# lowerkit.net
KiCad netlist of a schematic drawn in EAGLE
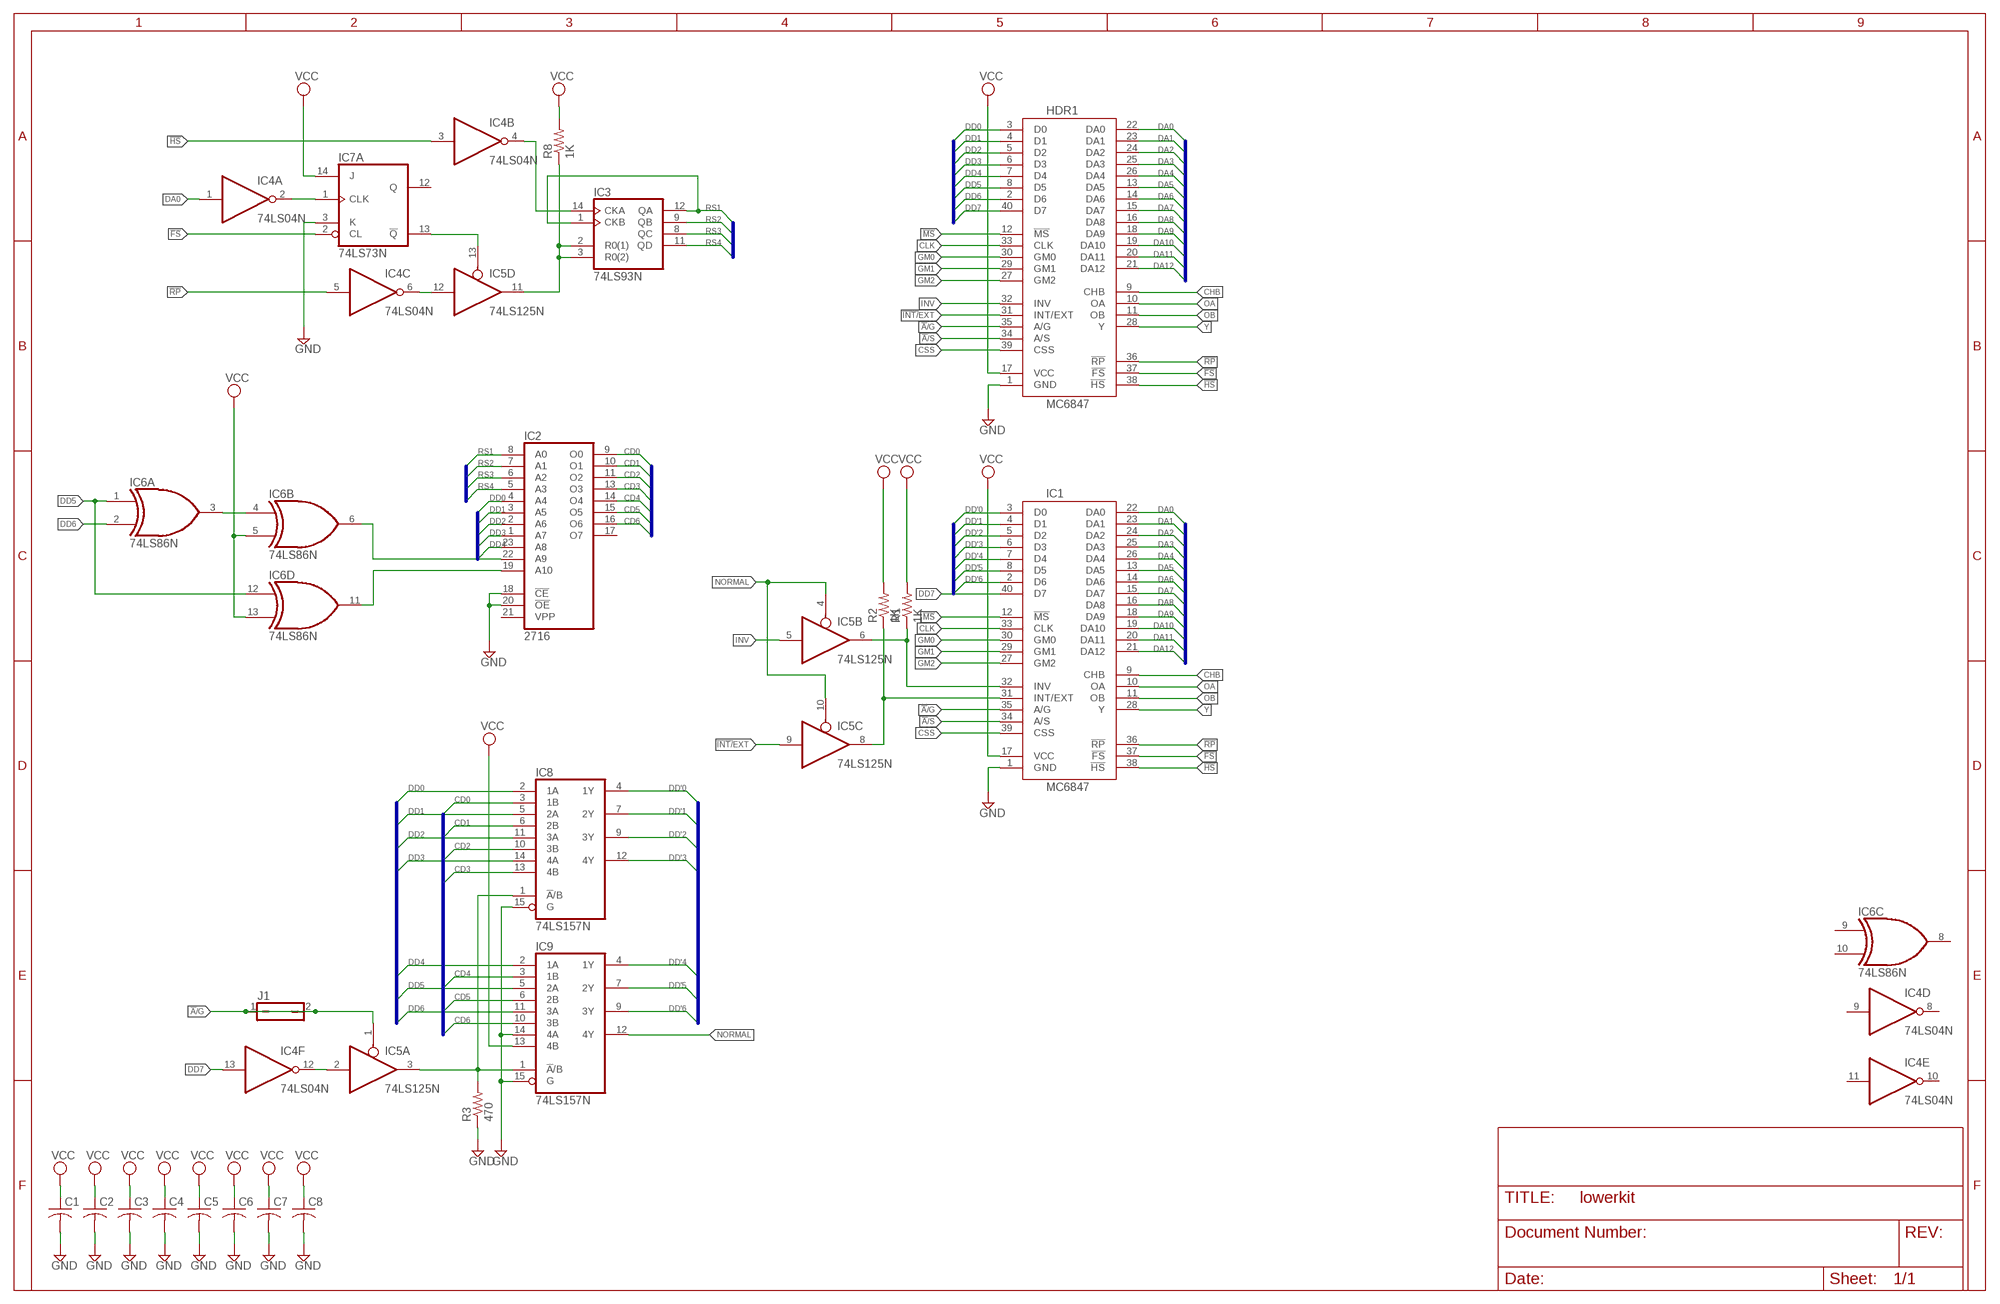
[diagram p0: schematic, sheet 1]

(export (version "E")
  (design (tool "Eeschema 10.0.6"))
  (components
    (comp (ref "C1")
      (value "C-US025-025X050")
      (footprint "eagle-import:C025-025X050")
      (libsource (lib "eagle-import") (part "C-US025-025X050"))
    )
    (comp (ref "C2")
      (value "C-US025-025X050")
      (footprint "eagle-import:C025-025X050")
      (libsource (lib "eagle-import") (part "C-US025-025X050"))
    )
    (comp (ref "C3")
      (value "C-US025-025X050")
      (footprint "eagle-import:C025-025X050")
      (libsource (lib "eagle-import") (part "C-US025-025X050"))
    )
    (comp (ref "C4")
      (value "C-US025-025X050")
      (footprint "eagle-import:C025-025X050")
      (libsource (lib "eagle-import") (part "C-US025-025X050"))
    )
    (comp (ref "C5")
      (value "C-US025-025X050")
      (footprint "eagle-import:C025-025X050")
      (libsource (lib "eagle-import") (part "C-US025-025X050"))
    )
    (comp (ref "C6")
      (value "C-US025-025X050")
      (footprint "eagle-import:C025-025X050")
      (libsource (lib "eagle-import") (part "C-US025-025X050"))
    )
    (comp (ref "C7")
      (value "C-US025-025X050")
      (footprint "eagle-import:C025-025X050")
      (libsource (lib "eagle-import") (part "C-US025-025X050"))
    )
    (comp (ref "C8")
      (value "C-US025-025X050")
      (footprint "eagle-import:C025-025X050")
      (libsource (lib "eagle-import") (part "C-US025-025X050"))
    )
    (comp (ref "HDR1")
      (value "MC6847")
      (footprint "eagle-import:DIP-40")
      (libsource (lib "eagle-import") (part "MC6847"))
    )
    (comp (ref "IC1")
      (value "MC6847")
      (footprint "eagle-import:DIP-40")
      (libsource (lib "eagle-import") (part "MC6847"))
    )
    (comp (ref "IC2")
      (value "2716")
      (footprint "eagle-import:DIL24")
      (libsource (lib "eagle-import") (part "2716"))
    )
    (comp (ref "IC3")
      (value "74LS93N")
      (footprint "eagle-import:DIL14-RP")
      (libsource (lib "eagle-import") (part "7493NLS"))
    )
    (comp (ref "IC4")
      (value "74LS04N")
      (footprint "eagle-import:DIL14-RP")
      (libsource (lib "eagle-import") (part "7404NLS"))
    )
    (comp (ref "IC5")
      (value "74LS125N")
      (footprint "eagle-import:DIL14-RP")
      (libsource (lib "eagle-import") (part "74125NLS"))
    )
    (comp (ref "IC6")
      (value "74LS86N")
      (footprint "eagle-import:DIL14-RP")
      (libsource (lib "eagle-import") (part "7486NLS"))
    )
    (comp (ref "IC7")
      (value "74LS73N")
      (footprint "eagle-import:DIL14-RP")
      (libsource (lib "eagle-import") (part "7473NLS"))
    )
    (comp (ref "IC8")
      (value "74LS157N")
      (footprint "eagle-import:DIL16-RP")
      (libsource (lib "eagle-import") (part "74157NLS"))
    )
    (comp (ref "IC9")
      (value "74LS157N")
      (footprint "eagle-import:DIL16-RP")
      (libsource (lib "eagle-import") (part "74157NLS"))
    )
    (comp (ref "J1")
      (value "JP1Q")
      (footprint "eagle-import:JP1")
      (libsource (lib "eagle-import") (part "JP1Q"))
    )
    (comp (ref "R1")
      (value "1K")
      (footprint "eagle-import:0204_7")
      (libsource (lib "eagle-import") (part "R-US_0204/7"))
    )
    (comp (ref "R2")
      (value "1K")
      (footprint "eagle-import:0204_7")
      (libsource (lib "eagle-import") (part "R-US_0204/7"))
    )
    (comp (ref "R3")
      (value "470")
      (footprint "eagle-import:0204_7")
      (libsource (lib "eagle-import") (part "R-US_0204/7"))
    )
    (comp (ref "R8")
      (value "1K")
      (footprint "eagle-import:0204_7")
      (libsource (lib "eagle-import") (part "R-US_0204/7"))
    )
  )
  (nets
    (net (code "1") (name "/CD0") (class "Default")
      (node (ref "IC2") (pin "9") (pinfunction "O0_9") (pintype "tri_state"))
      (node (ref "IC8") (pin "3") (pinfunction "1B_3") (pintype "input"))
    )
    (net (code "2") (name "/CD1") (class "Default")
      (node (ref "IC2") (pin "10") (pinfunction "O1_10") (pintype "tri_state"))
      (node (ref "IC8") (pin "6") (pinfunction "2B_6") (pintype "input"))
    )
    (net (code "3") (name "/CD2") (class "Default")
      (node (ref "IC2") (pin "11") (pinfunction "O2_11") (pintype "tri_state"))
      (node (ref "IC8") (pin "10") (pinfunction "3B_10") (pintype "input"))
    )
    (net (code "4") (name "/CD3") (class "Default")
      (node (ref "IC2") (pin "13") (pinfunction "O3_13") (pintype "tri_state"))
      (node (ref "IC8") (pin "13") (pinfunction "4B_13") (pintype "input"))
    )
    (net (code "5") (name "/CD4") (class "Default")
      (node (ref "IC2") (pin "14") (pinfunction "O4_14") (pintype "tri_state"))
      (node (ref "IC9") (pin "3") (pinfunction "1B_3") (pintype "input"))
    )
    (net (code "6") (name "/CD5") (class "Default")
      (node (ref "IC2") (pin "15") (pinfunction "O5_15") (pintype "tri_state"))
      (node (ref "IC9") (pin "6") (pinfunction "2B_6") (pintype "input"))
    )
    (net (code "7") (name "/CD6") (class "Default")
      (node (ref "IC2") (pin "16") (pinfunction "O6_16") (pintype "tri_state"))
      (node (ref "IC9") (pin "10") (pinfunction "3B_10") (pintype "input"))
    )
    (net (code "8") (name "/DA1") (class "Default")
      (node (ref "HDR1") (pin "23") (pinfunction "DA1_23") (pintype "bidirectional"))
      (node (ref "IC1") (pin "23") (pinfunction "DA1_23") (pintype "bidirectional"))
    )
    (net (code "9") (name "/DA2") (class "Default")
      (node (ref "HDR1") (pin "24") (pinfunction "DA2_24") (pintype "bidirectional"))
      (node (ref "IC1") (pin "24") (pinfunction "DA2_24") (pintype "bidirectional"))
    )
    (net (code "10") (name "/DA3") (class "Default")
      (node (ref "HDR1") (pin "25") (pinfunction "DA3_25") (pintype "bidirectional"))
      (node (ref "IC1") (pin "25") (pinfunction "DA3_25") (pintype "bidirectional"))
    )
    (net (code "11") (name "/DA4") (class "Default")
      (node (ref "HDR1") (pin "26") (pinfunction "DA4_26") (pintype "bidirectional"))
      (node (ref "IC1") (pin "26") (pinfunction "DA4_26") (pintype "bidirectional"))
    )
    (net (code "12") (name "/DA5") (class "Default")
      (node (ref "HDR1") (pin "13") (pinfunction "DA5_13") (pintype "bidirectional"))
      (node (ref "IC1") (pin "13") (pinfunction "DA5_13") (pintype "bidirectional"))
    )
    (net (code "13") (name "/DA6") (class "Default")
      (node (ref "HDR1") (pin "14") (pinfunction "DA6_14") (pintype "bidirectional"))
      (node (ref "IC1") (pin "14") (pinfunction "DA6_14") (pintype "bidirectional"))
    )
    (net (code "14") (name "/DA7") (class "Default")
      (node (ref "HDR1") (pin "15") (pinfunction "DA7_15") (pintype "bidirectional"))
      (node (ref "IC1") (pin "15") (pinfunction "DA7_15") (pintype "bidirectional"))
    )
    (net (code "15") (name "/DA8") (class "Default")
      (node (ref "HDR1") (pin "16") (pinfunction "DA8_16") (pintype "bidirectional"))
      (node (ref "IC1") (pin "16") (pinfunction "DA8_16") (pintype "bidirectional"))
    )
    (net (code "16") (name "/DA9") (class "Default")
      (node (ref "HDR1") (pin "18") (pinfunction "DA9_18") (pintype "bidirectional"))
      (node (ref "IC1") (pin "18") (pinfunction "DA9_18") (pintype "bidirectional"))
    )
    (net (code "17") (name "/DA10") (class "Default")
      (node (ref "HDR1") (pin "19") (pinfunction "DA10_19") (pintype "bidirectional"))
      (node (ref "IC1") (pin "19") (pinfunction "DA10_19") (pintype "bidirectional"))
    )
    (net (code "18") (name "/DA11") (class "Default")
      (node (ref "HDR1") (pin "20") (pinfunction "DA11_20") (pintype "bidirectional"))
      (node (ref "IC1") (pin "20") (pinfunction "DA11_20") (pintype "bidirectional"))
    )
    (net (code "19") (name "/DA12") (class "Default")
      (node (ref "HDR1") (pin "21") (pinfunction "DA12_21") (pintype "bidirectional"))
      (node (ref "IC1") (pin "21") (pinfunction "DA12_21") (pintype "bidirectional"))
    )
    (net (code "20") (name "/DD'0") (class "Default")
      (node (ref "IC1") (pin "3") (pinfunction "D0_3") (pintype "bidirectional"))
      (node (ref "IC8") (pin "4") (pinfunction "1Y_4") (pintype "output"))
    )
    (net (code "21") (name "/DD'1") (class "Default")
      (node (ref "IC1") (pin "4") (pinfunction "D1_4") (pintype "bidirectional"))
      (node (ref "IC8") (pin "7") (pinfunction "2Y_7") (pintype "output"))
    )
    (net (code "22") (name "/DD'2") (class "Default")
      (node (ref "IC1") (pin "5") (pinfunction "D2_5") (pintype "bidirectional"))
      (node (ref "IC8") (pin "9") (pinfunction "3Y_9") (pintype "output"))
    )
    (net (code "23") (name "/DD'3") (class "Default")
      (node (ref "IC1") (pin "6") (pinfunction "D3_6") (pintype "bidirectional"))
      (node (ref "IC8") (pin "12") (pinfunction "4Y_12") (pintype "output"))
    )
    (net (code "24") (name "/DD'4") (class "Default")
      (node (ref "IC1") (pin "7") (pinfunction "D4_7") (pintype "bidirectional"))
      (node (ref "IC9") (pin "4") (pinfunction "1Y_4") (pintype "output"))
    )
    (net (code "25") (name "/DD'5") (class "Default")
      (node (ref "IC1") (pin "8") (pinfunction "D5_8") (pintype "bidirectional"))
      (node (ref "IC9") (pin "7") (pinfunction "2Y_7") (pintype "output"))
    )
    (net (code "26") (name "/DD'6") (class "Default")
      (node (ref "IC1") (pin "2") (pinfunction "D6_2") (pintype "bidirectional"))
      (node (ref "IC9") (pin "9") (pinfunction "3Y_9") (pintype "output"))
    )
    (net (code "27") (name "/DD0") (class "Default")
      (node (ref "HDR1") (pin "3") (pinfunction "D0_3") (pintype "bidirectional"))
      (node (ref "IC2") (pin "4") (pinfunction "A4_4") (pintype "input"))
      (node (ref "IC8") (pin "2") (pinfunction "1A_2") (pintype "input"))
    )
    (net (code "28") (name "/DD1") (class "Default")
      (node (ref "HDR1") (pin "4") (pinfunction "D1_4") (pintype "bidirectional"))
      (node (ref "IC2") (pin "3") (pinfunction "A5_3") (pintype "input"))
      (node (ref "IC8") (pin "5") (pinfunction "2A_5") (pintype "input"))
    )
    (net (code "29") (name "/DD2") (class "Default")
      (node (ref "HDR1") (pin "5") (pinfunction "D2_5") (pintype "bidirectional"))
      (node (ref "IC2") (pin "2") (pinfunction "A6_2") (pintype "input"))
      (node (ref "IC8") (pin "11") (pinfunction "3A_11") (pintype "input"))
    )
    (net (code "30") (name "/DD3") (class "Default")
      (node (ref "HDR1") (pin "6") (pinfunction "D3_6") (pintype "bidirectional"))
      (node (ref "IC2") (pin "1") (pinfunction "A7_1") (pintype "input"))
      (node (ref "IC8") (pin "14") (pinfunction "4A_14") (pintype "input"))
    )
    (net (code "31") (name "/DD4") (class "Default")
      (node (ref "HDR1") (pin "7") (pinfunction "D4_7") (pintype "bidirectional"))
      (node (ref "IC2") (pin "23") (pinfunction "A8_23") (pintype "input"))
      (node (ref "IC9") (pin "2") (pinfunction "1A_2") (pintype "input"))
    )
    (net (code "32") (name "/RS1") (class "Default")
      (node (ref "IC2") (pin "8") (pinfunction "A0_8") (pintype "input"))
      (node (ref "IC3") (pin "1") (pinfunction "CKB_1") (pintype "input"))
      (node (ref "IC3") (pin "12") (pinfunction "QA_12") (pintype "output"))
    )
    (net (code "33") (name "/RS2") (class "Default")
      (node (ref "IC2") (pin "7") (pinfunction "A1_7") (pintype "input"))
      (node (ref "IC3") (pin "9") (pinfunction "QB_9") (pintype "output"))
    )
    (net (code "34") (name "/RS3") (class "Default")
      (node (ref "IC2") (pin "6") (pinfunction "A2_6") (pintype "input"))
      (node (ref "IC3") (pin "8") (pinfunction "QC_8") (pintype "output"))
    )
    (net (code "35") (name "/RS4") (class "Default")
      (node (ref "IC2") (pin "5") (pinfunction "A3_5") (pintype "input"))
      (node (ref "IC3") (pin "11") (pinfunction "QD_11") (pintype "output"))
    )
    (net (code "36") (name "/~{A}{slash}G") (class "Default")
      (node (ref "HDR1") (pin "35") (pinfunction "A/G_35") (pintype "bidirectional"))
      (node (ref "IC1") (pin "35") (pinfunction "A/G_35") (pintype "bidirectional"))
      (node (ref "IC5") (pin "1") (pinfunction "OE_1") (pintype "input"))
      (node (ref "J1") (pin "1") (pinfunction "1_1") (pintype "passive"))
      (node (ref "J1") (pin "2") (pinfunction "2_2") (pintype "passive"))
    )
    (net (code "37") (name "/~{A}{slash}S") (class "Default")
      (node (ref "HDR1") (pin "34") (pinfunction "A/S_34") (pintype "bidirectional"))
      (node (ref "IC1") (pin "34") (pinfunction "A/S_34") (pintype "bidirectional"))
    )
    (net (code "38") (name "/~{FS}") (class "Default")
      (node (ref "HDR1") (pin "37") (pinfunction "~{FS}_37") (pintype "bidirectional"))
      (node (ref "IC1") (pin "37") (pinfunction "~{FS}_37") (pintype "bidirectional"))
      (node (ref "IC7") (pin "2") (pinfunction "CL_2") (pintype "input"))
    )
    (net (code "39") (name "/~{HS}") (class "Default")
      (node (ref "HDR1") (pin "38") (pinfunction "~{HS}_38") (pintype "bidirectional"))
      (node (ref "IC1") (pin "38") (pinfunction "~{HS}_38") (pintype "bidirectional"))
      (node (ref "IC4") (pin "3") (pinfunction "I_3") (pintype "input"))
    )
    (net (code "40") (name "/~{INT{slash}}EXT") (class "Default")
      (node (ref "HDR1") (pin "31") (pinfunction "INT/EXT_31") (pintype "bidirectional"))
      (node (ref "IC5") (pin "9") (pinfunction "I_9") (pintype "input"))
    )
    (net (code "41") (name "/~{MS}") (class "Default")
      (node (ref "HDR1") (pin "12") (pinfunction "~{MS}_12") (pintype "bidirectional"))
      (node (ref "IC1") (pin "12") (pinfunction "~{MS}_12") (pintype "bidirectional"))
    )
    (net (code "42") (name "/~{RP}") (class "Default")
      (node (ref "HDR1") (pin "36") (pinfunction "~{RP}_36") (pintype "bidirectional"))
      (node (ref "IC1") (pin "36") (pinfunction "~{RP}_36") (pintype "bidirectional"))
      (node (ref "IC4") (pin "5") (pinfunction "I_5") (pintype "input"))
    )
    (net (code "43") (name "CHB") (class "Default")
      (node (ref "HDR1") (pin "9") (pinfunction "CHB_9") (pintype "bidirectional"))
      (node (ref "IC1") (pin "9") (pinfunction "CHB_9") (pintype "bidirectional"))
    )
    (net (code "44") (name "CLK") (class "Default")
      (node (ref "HDR1") (pin "33") (pinfunction "CLK_33") (pintype "bidirectional"))
      (node (ref "IC1") (pin "33") (pinfunction "CLK_33") (pintype "bidirectional"))
    )
    (net (code "45") (name "CSS") (class "Default")
      (node (ref "HDR1") (pin "39") (pinfunction "CSS_39") (pintype "bidirectional"))
      (node (ref "IC1") (pin "39") (pinfunction "CSS_39") (pintype "bidirectional"))
    )
    (net (code "46") (name "DA0") (class "Default")
      (node (ref "HDR1") (pin "22") (pinfunction "DA0_22") (pintype "bidirectional"))
      (node (ref "IC1") (pin "22") (pinfunction "DA0_22") (pintype "bidirectional"))
      (node (ref "IC4") (pin "1") (pinfunction "I_1") (pintype "input"))
    )
    (net (code "47") (name "DD5") (class "Default")
      (node (ref "HDR1") (pin "8") (pinfunction "D5_8") (pintype "bidirectional"))
      (node (ref "IC6") (pin "1") (pinfunction "I0_1") (pintype "input"))
      (node (ref "IC6") (pin "12") (pinfunction "I0_12") (pintype "input"))
      (node (ref "IC9") (pin "5") (pinfunction "2A_5") (pintype "input"))
    )
    (net (code "48") (name "DD6") (class "Default")
      (node (ref "HDR1") (pin "2") (pinfunction "D6_2") (pintype "bidirectional"))
      (node (ref "IC6") (pin "2") (pinfunction "I1_2") (pintype "input"))
      (node (ref "IC9") (pin "11") (pinfunction "3A_11") (pintype "input"))
    )
    (net (code "49") (name "DD7") (class "Default")
      (node (ref "HDR1") (pin "40") (pinfunction "D7_40") (pintype "bidirectional"))
      (node (ref "IC1") (pin "40") (pinfunction "D7_40") (pintype "bidirectional"))
      (node (ref "IC4") (pin "13") (pinfunction "I_13") (pintype "input"))
    )
    (net (code "50") (name "GM0") (class "Default")
      (node (ref "HDR1") (pin "30") (pinfunction "GM0_30") (pintype "bidirectional"))
      (node (ref "IC1") (pin "30") (pinfunction "GM0_30") (pintype "bidirectional"))
    )
    (net (code "51") (name "GM1") (class "Default")
      (node (ref "HDR1") (pin "29") (pinfunction "GM1_29") (pintype "bidirectional"))
      (node (ref "IC1") (pin "29") (pinfunction "GM1_29") (pintype "bidirectional"))
    )
    (net (code "52") (name "GM2") (class "Default")
      (node (ref "HDR1") (pin "27") (pinfunction "GM2_27") (pintype "bidirectional"))
      (node (ref "IC1") (pin "27") (pinfunction "GM2_27") (pintype "bidirectional"))
    )
    (net (code "53") (name "GND") (class "Default")
      (node (ref "C1") (pin "2") (pinfunction "2_2") (pintype "passive"))
      (node (ref "C2") (pin "2") (pinfunction "2_2") (pintype "passive"))
      (node (ref "C3") (pin "2") (pinfunction "2_2") (pintype "passive"))
      (node (ref "C4") (pin "2") (pinfunction "2_2") (pintype "passive"))
      (node (ref "C5") (pin "2") (pinfunction "2_2") (pintype "passive"))
      (node (ref "C6") (pin "2") (pinfunction "2_2") (pintype "passive"))
      (node (ref "C7") (pin "2") (pinfunction "2_2") (pintype "passive"))
      (node (ref "C8") (pin "2") (pinfunction "2_2") (pintype "passive"))
      (node (ref "HDR1") (pin "1") (pinfunction "GND_1") (pintype "bidirectional"))
      (node (ref "IC1") (pin "1") (pinfunction "GND_1") (pintype "bidirectional"))
      (node (ref "IC2") (pin "18") (pinfunction "~{CE}_18") (pintype "input"))
      (node (ref "IC2") (pin "20") (pinfunction "~{OE}_20") (pintype "input"))
      (node (ref "IC7") (pin "3") (pinfunction "K_3") (pintype "input"))
      (node (ref "IC8") (pin "15") (pinfunction "G_15") (pintype "input"))
      (node (ref "IC9") (pin "14") (pinfunction "4A_14") (pintype "input"))
      (node (ref "IC9") (pin "15") (pinfunction "G_15") (pintype "input"))
      (node (ref "R3") (pin "1") (pinfunction "1_1") (pintype "passive"))
    )
    (net (code "54") (name "INV") (class "Default")
      (node (ref "HDR1") (pin "32") (pinfunction "INV_32") (pintype "bidirectional"))
      (node (ref "IC5") (pin "5") (pinfunction "I_5") (pintype "input"))
    )
    (net (code "55") (name "NORMAL") (class "Default")
      (node (ref "IC5") (pin "10") (pinfunction "OE_10") (pintype "input"))
      (node (ref "IC5") (pin "4") (pinfunction "OE_4") (pintype "input"))
      (node (ref "IC9") (pin "12") (pinfunction "4Y_12") (pintype "output"))
    )
    (net (code "56") (name "Net-(IC1-INT{slash}EXT)") (class "Default")
      (node (ref "IC1") (pin "31") (pinfunction "INT/EXT_31") (pintype "bidirectional"))
      (node (ref "IC5") (pin "8") (pinfunction "O_8") (pintype "tri_state"))
      (node (ref "R2") (pin "1") (pinfunction "1_1") (pintype "passive"))
    )
    (net (code "57") (name "Net-(IC1-INV)") (class "Default")
      (node (ref "IC1") (pin "32") (pinfunction "INV_32") (pintype "bidirectional"))
      (node (ref "IC5") (pin "6") (pinfunction "O_6") (pintype "tri_state"))
      (node (ref "R1") (pin "1") (pinfunction "1_1") (pintype "passive"))
    )
    (net (code "58") (name "Net-(IC2A-A9)") (class "Default")
      (node (ref "IC2") (pin "22") (pinfunction "A9_22") (pintype "input"))
      (node (ref "IC6") (pin "6") (pinfunction "O_6") (pintype "output"))
    )
    (net (code "59") (name "Net-(IC2A-A10)") (class "Default")
      (node (ref "IC2") (pin "19") (pinfunction "A10_19") (pintype "input"))
      (node (ref "IC6") (pin "11") (pinfunction "O_11") (pintype "output"))
    )
    (net (code "60") (name "Net-(IC3A-CKA)") (class "Default")
      (node (ref "IC3") (pin "14") (pinfunction "CKA_14") (pintype "input"))
      (node (ref "IC4") (pin "4") (pinfunction "O_4") (pintype "output"))
    )
    (net (code "61") (name "Net-(IC3A-R0(1))") (class "Default")
      (node (ref "IC3") (pin "2") (pinfunction "R0(1)_2") (pintype "input"))
      (node (ref "IC3") (pin "3") (pinfunction "R0(2)_3") (pintype "input"))
      (node (ref "IC5") (pin "11") (pinfunction "O_11") (pintype "tri_state"))
      (node (ref "R8") (pin "1") (pinfunction "1_1") (pintype "passive"))
    )
    (net (code "62") (name "Net-(IC4A-O)") (class "Default")
      (node (ref "IC4") (pin "2") (pinfunction "O_2") (pintype "output"))
      (node (ref "IC7") (pin "1") (pinfunction "CLK_1") (pintype "input"))
    )
    (net (code "63") (name "Net-(IC4C-O)") (class "Default")
      (node (ref "IC4") (pin "6") (pinfunction "O_6") (pintype "output"))
      (node (ref "IC5") (pin "12") (pinfunction "I_12") (pintype "input"))
    )
    (net (code "64") (name "Net-(IC4F-O)") (class "Default")
      (node (ref "IC4") (pin "12") (pinfunction "O_12") (pintype "output"))
      (node (ref "IC5") (pin "2") (pinfunction "I_2") (pintype "input"))
    )
    (net (code "65") (name "Net-(IC5A-O)") (class "Default")
      (node (ref "IC5") (pin "3") (pinfunction "O_3") (pintype "tri_state"))
      (node (ref "IC8") (pin "1") (pinfunction "~{A}/B_1") (pintype "input"))
      (node (ref "IC9") (pin "1") (pinfunction "~{A}/B_1") (pintype "input"))
      (node (ref "R3") (pin "2") (pinfunction "2_2") (pintype "passive"))
    )
    (net (code "66") (name "Net-(IC5D-OE)") (class "Default")
      (node (ref "IC5") (pin "13") (pinfunction "OE_13") (pintype "input"))
      (node (ref "IC7") (pin "13") (pinfunction "~{Q}_13") (pintype "output"))
    )
    (net (code "67") (name "Net-(IC6A-O)") (class "Default")
      (node (ref "IC6") (pin "3") (pinfunction "O_3") (pintype "output"))
      (node (ref "IC6") (pin "4") (pinfunction "I0_4") (pintype "input"))
    )
    (net (code "68") (name "OA") (class "Default")
      (node (ref "HDR1") (pin "10") (pinfunction "OA_10") (pintype "bidirectional"))
      (node (ref "IC1") (pin "10") (pinfunction "OA_10") (pintype "bidirectional"))
    )
    (net (code "69") (name "OB") (class "Default")
      (node (ref "HDR1") (pin "11") (pinfunction "OB_11") (pintype "bidirectional"))
      (node (ref "IC1") (pin "11") (pinfunction "OB_11") (pintype "bidirectional"))
    )
    (net (code "70") (name "VCC") (class "Default")
      (node (ref "C1") (pin "1") (pinfunction "1_1") (pintype "passive"))
      (node (ref "C2") (pin "1") (pinfunction "1_1") (pintype "passive"))
      (node (ref "C3") (pin "1") (pinfunction "1_1") (pintype "passive"))
      (node (ref "C4") (pin "1") (pinfunction "1_1") (pintype "passive"))
      (node (ref "C5") (pin "1") (pinfunction "1_1") (pintype "passive"))
      (node (ref "C6") (pin "1") (pinfunction "1_1") (pintype "passive"))
      (node (ref "C7") (pin "1") (pinfunction "1_1") (pintype "passive"))
      (node (ref "C8") (pin "1") (pinfunction "1_1") (pintype "passive"))
      (node (ref "HDR1") (pin "17") (pinfunction "VCC_17") (pintype "bidirectional"))
      (node (ref "IC1") (pin "17") (pinfunction "VCC_17") (pintype "bidirectional"))
      (node (ref "IC6") (pin "13") (pinfunction "I1_13") (pintype "input"))
      (node (ref "IC6") (pin "5") (pinfunction "I1_5") (pintype "input"))
      (node (ref "IC7") (pin "14") (pinfunction "J_14") (pintype "input"))
      (node (ref "IC9") (pin "13") (pinfunction "4B_13") (pintype "input"))
      (node (ref "R1") (pin "2") (pinfunction "2_2") (pintype "passive"))
      (node (ref "R2") (pin "2") (pinfunction "2_2") (pintype "passive"))
      (node (ref "R8") (pin "2") (pinfunction "2_2") (pintype "passive"))
    )
    (net (code "71") (name "Y") (class "Default")
      (node (ref "HDR1") (pin "28") (pinfunction "Y_28") (pintype "bidirectional"))
      (node (ref "IC1") (pin "28") (pinfunction "Y_28") (pintype "bidirectional"))
    )
    (net (code "72") (name "unconnected-(IC2A-O7-Pad17)") (class "Default")
      (node (ref "IC2") (pin "17") (pinfunction "O7_17") (pintype "tri_state"))
    )
    (net (code "73") (name "unconnected-(IC2A-VPP-Pad21)") (class "Default")
      (node (ref "IC2") (pin "21") (pinfunction "VPP_21") (pintype "input"))
    )
    (net (code "74") (name "unconnected-(IC4D-I-Pad9)") (class "Default")
      (node (ref "IC4") (pin "9") (pinfunction "I_9") (pintype "input"))
    )
    (net (code "75") (name "unconnected-(IC4D-O-Pad8)") (class "Default")
      (node (ref "IC4") (pin "8") (pinfunction "O_8") (pintype "output"))
    )
    (net (code "76") (name "unconnected-(IC4E-I-Pad11)") (class "Default")
      (node (ref "IC4") (pin "11") (pinfunction "I_11") (pintype "input"))
    )
    (net (code "77") (name "unconnected-(IC4E-O-Pad10)") (class "Default")
      (node (ref "IC4") (pin "10") (pinfunction "O_10") (pintype "output"))
    )
    (net (code "78") (name "unconnected-(IC6C-I0-Pad9)") (class "Default")
      (node (ref "IC6") (pin "9") (pinfunction "I0_9") (pintype "input"))
    )
    (net (code "79") (name "unconnected-(IC6C-I1-Pad10)") (class "Default")
      (node (ref "IC6") (pin "10") (pinfunction "I1_10") (pintype "input"))
    )
    (net (code "80") (name "unconnected-(IC6C-O-Pad8)") (class "Default")
      (node (ref "IC6") (pin "8") (pinfunction "O_8") (pintype "output"))
    )
    (net (code "81") (name "unconnected-(IC7A-Q-Pad12)") (class "Default")
      (node (ref "IC7") (pin "12") (pinfunction "Q_12") (pintype "output"))
    )
  )
)
